# Connector.net
KiCad netlist of a schematic drawn in Altium Designer
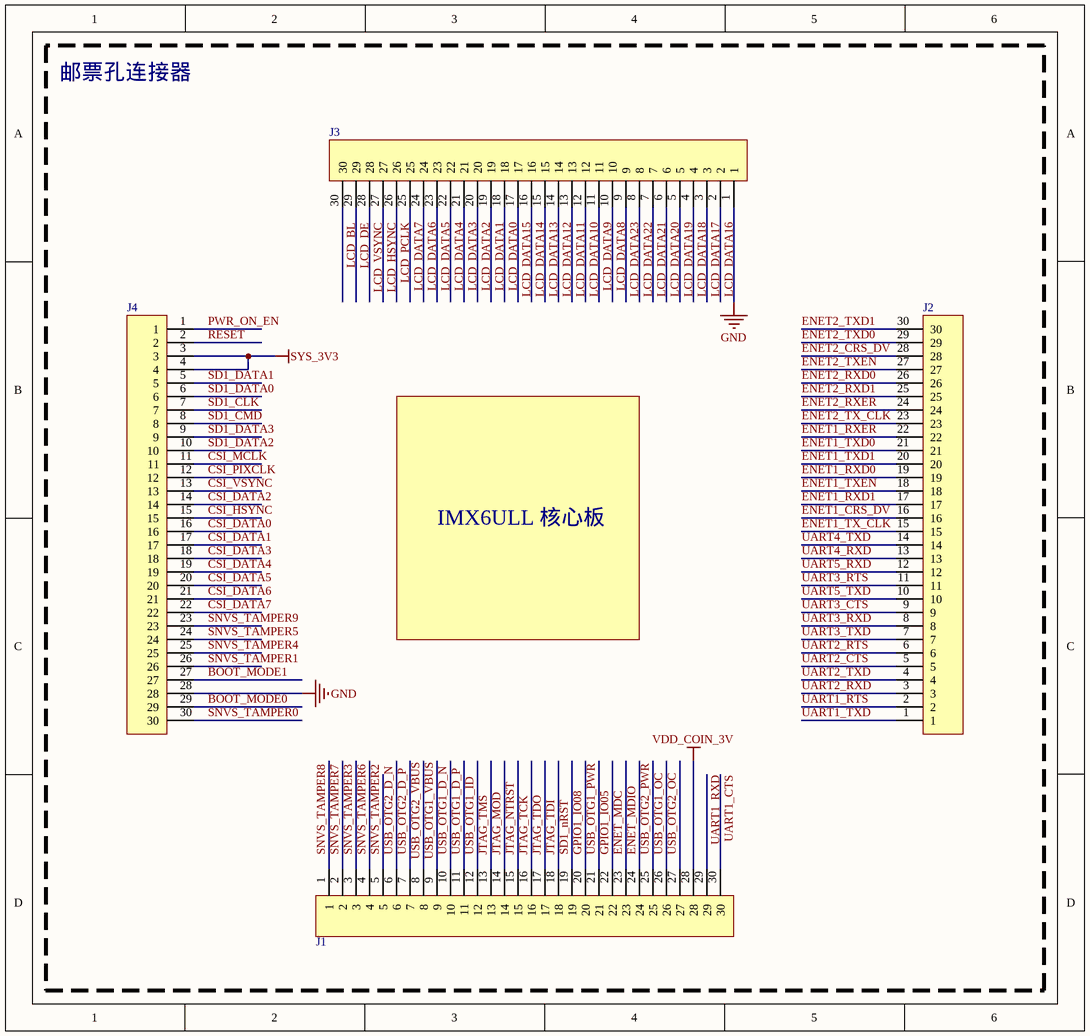
[diagram p0: Connector.SchDoc]

(export (version "E")
  (design (tool "Eeschema 10.0.6"))
  (components
    (comp (ref "J1")
      (value "stamp_hole_30")
      (footprint "STAMP_HOLE_30")
      (libsource (lib "") (part "stamp_hole_30_3"))
    )
    (comp (ref "J2")
      (value "stamp_hole_30")
      (footprint "STAMP_HOLE_30")
      (libsource (lib "Linux_Base") (part "stamp_hole_30"))
    )
    (comp (ref "J3")
      (value "stamp_hole_30")
      (footprint "STAMP_HOLE_30")
      (libsource (lib "") (part "stamp_hole_30_2"))
    )
    (comp (ref "J4")
      (value "stamp_hole_30")
      (footprint "STAMP_HOLE_30")
      (libsource (lib "") (part "stamp_hole_30_1"))
    )
  )
  (nets
    (net (code "1") (name "/BOOT_MODE0") (class "Default")
      (node (ref "J4") (pin "29") (pinfunction "29_29") (pintype "passive"))
    )
    (net (code "2") (name "/BOOT_MODE1") (class "Default")
      (node (ref "J4") (pin "27") (pinfunction "27_27") (pintype "passive"))
    )
    (net (code "3") (name "/CSI_DATA0") (class "Default")
      (node (ref "J4") (pin "16") (pinfunction "16_16") (pintype "passive"))
    )
    (net (code "4") (name "/CSI_DATA1") (class "Default")
      (node (ref "J4") (pin "17") (pinfunction "17_17") (pintype "passive"))
    )
    (net (code "5") (name "/CSI_DATA2") (class "Default")
      (node (ref "J4") (pin "14") (pinfunction "14_14") (pintype "passive"))
    )
    (net (code "6") (name "/CSI_DATA3") (class "Default")
      (node (ref "J4") (pin "18") (pinfunction "18_18") (pintype "passive"))
    )
    (net (code "7") (name "/CSI_DATA4") (class "Default")
      (node (ref "J4") (pin "19") (pinfunction "19_19") (pintype "passive"))
    )
    (net (code "8") (name "/CSI_DATA5") (class "Default")
      (node (ref "J4") (pin "20") (pinfunction "20_20") (pintype "passive"))
    )
    (net (code "9") (name "/CSI_DATA6") (class "Default")
      (node (ref "J4") (pin "21") (pinfunction "21_21") (pintype "passive"))
    )
    (net (code "10") (name "/CSI_DATA7") (class "Default")
      (node (ref "J4") (pin "22") (pinfunction "22_22") (pintype "passive"))
    )
    (net (code "11") (name "/CSI_HSYNC") (class "Default")
      (node (ref "J4") (pin "15") (pinfunction "15_15") (pintype "passive"))
    )
    (net (code "12") (name "/CSI_MCLK") (class "Default")
      (node (ref "J4") (pin "11") (pinfunction "11_11") (pintype "passive"))
    )
    (net (code "13") (name "/CSI_PIXCLK") (class "Default")
      (node (ref "J4") (pin "12") (pinfunction "12_12") (pintype "passive"))
    )
    (net (code "14") (name "/CSI_VSYNC") (class "Default")
      (node (ref "J4") (pin "13") (pinfunction "13_13") (pintype "passive"))
    )
    (net (code "15") (name "/ENET1_CRS_DV") (class "Default")
      (node (ref "J2") (pin "16") (pinfunction "16_16") (pintype "passive"))
    )
    (net (code "16") (name "/ENET1_RXD0") (class "Default")
      (node (ref "J2") (pin "19") (pinfunction "19_19") (pintype "passive"))
    )
    (net (code "17") (name "/ENET1_RXD1") (class "Default")
      (node (ref "J2") (pin "17") (pinfunction "17_17") (pintype "passive"))
    )
    (net (code "18") (name "/ENET1_RXER") (class "Default")
      (node (ref "J2") (pin "22") (pinfunction "22_22") (pintype "passive"))
    )
    (net (code "19") (name "/ENET1_TXD0") (class "Default")
      (node (ref "J2") (pin "21") (pinfunction "21_21") (pintype "passive"))
    )
    (net (code "20") (name "/ENET1_TXD1") (class "Default")
      (node (ref "J2") (pin "20") (pinfunction "20_20") (pintype "passive"))
    )
    (net (code "21") (name "/ENET1_TXEN") (class "Default")
      (node (ref "J2") (pin "18") (pinfunction "18_18") (pintype "passive"))
    )
    (net (code "22") (name "/ENET1_TX_CLK") (class "Default")
      (node (ref "J2") (pin "15") (pinfunction "15_15") (pintype "passive"))
    )
    (net (code "23") (name "/ENET2_CRS_DV") (class "Default")
      (node (ref "J2") (pin "28") (pinfunction "28_28") (pintype "passive"))
    )
    (net (code "24") (name "/ENET2_RXD0") (class "Default")
      (node (ref "J2") (pin "26") (pinfunction "26_26") (pintype "passive"))
    )
    (net (code "25") (name "/ENET2_RXD1") (class "Default")
      (node (ref "J2") (pin "25") (pinfunction "25_25") (pintype "passive"))
    )
    (net (code "26") (name "/ENET2_RXER") (class "Default")
      (node (ref "J2") (pin "24") (pinfunction "24_24") (pintype "passive"))
    )
    (net (code "27") (name "/ENET2_TXD0") (class "Default")
      (node (ref "J2") (pin "29") (pinfunction "29_29") (pintype "passive"))
    )
    (net (code "28") (name "/ENET2_TXD1") (class "Default")
      (node (ref "J2") (pin "30") (pinfunction "30_30") (pintype "passive"))
    )
    (net (code "29") (name "/ENET2_TXEN") (class "Default")
      (node (ref "J2") (pin "27") (pinfunction "27_27") (pintype "passive"))
    )
    (net (code "30") (name "/ENET2_TX_CLK") (class "Default")
      (node (ref "J2") (pin "23") (pinfunction "23_23") (pintype "passive"))
    )
    (net (code "31") (name "/ENET_MDC") (class "Default")
      (node (ref "J1") (pin "23") (pinfunction "23_23") (pintype "passive"))
    )
    (net (code "32") (name "/ENET_MDIO") (class "Default")
      (node (ref "J1") (pin "24") (pinfunction "24_24") (pintype "passive"))
    )
    (net (code "33") (name "/GPIO1_IO05") (class "Default")
      (node (ref "J1") (pin "22") (pinfunction "22_22") (pintype "passive"))
    )
    (net (code "34") (name "/GPIO1_IO08") (class "Default")
      (node (ref "J1") (pin "20") (pinfunction "20_20") (pintype "passive"))
    )
    (net (code "35") (name "/JTAG_MOD") (class "Default")
      (node (ref "J1") (pin "14") (pinfunction "14_14") (pintype "passive"))
    )
    (net (code "36") (name "/JTAG_NTRST") (class "Default")
      (node (ref "J1") (pin "15") (pinfunction "15_15") (pintype "passive"))
    )
    (net (code "37") (name "/JTAG_TCK") (class "Default")
      (node (ref "J1") (pin "16") (pinfunction "16_16") (pintype "passive"))
    )
    (net (code "38") (name "/JTAG_TDI") (class "Default")
      (node (ref "J1") (pin "18") (pinfunction "18_18") (pintype "passive"))
    )
    (net (code "39") (name "/JTAG_TDO") (class "Default")
      (node (ref "J1") (pin "17") (pinfunction "17_17") (pintype "passive"))
    )
    (net (code "40") (name "/JTAG_TMS") (class "Default")
      (node (ref "J1") (pin "13") (pinfunction "13_13") (pintype "passive"))
    )
    (net (code "41") (name "/LCD_BL") (class "Default")
      (node (ref "J3") (pin "30") (pinfunction "30_30") (pintype "passive"))
    )
    (net (code "42") (name "/LCD_DATA0") (class "Default")
      (node (ref "J3") (pin "18") (pinfunction "18_18") (pintype "passive"))
    )
    (net (code "43") (name "/LCD_DATA1") (class "Default")
      (node (ref "J3") (pin "19") (pinfunction "19_19") (pintype "passive"))
    )
    (net (code "44") (name "/LCD_DATA2") (class "Default")
      (node (ref "J3") (pin "20") (pinfunction "20_20") (pintype "passive"))
    )
    (net (code "45") (name "/LCD_DATA3") (class "Default")
      (node (ref "J3") (pin "21") (pinfunction "21_21") (pintype "passive"))
    )
    (net (code "46") (name "/LCD_DATA4") (class "Default")
      (node (ref "J3") (pin "22") (pinfunction "22_22") (pintype "passive"))
    )
    (net (code "47") (name "/LCD_DATA5") (class "Default")
      (node (ref "J3") (pin "23") (pinfunction "23_23") (pintype "passive"))
    )
    (net (code "48") (name "/LCD_DATA6") (class "Default")
      (node (ref "J3") (pin "24") (pinfunction "24_24") (pintype "passive"))
    )
    (net (code "49") (name "/LCD_DATA7") (class "Default")
      (node (ref "J3") (pin "25") (pinfunction "25_25") (pintype "passive"))
    )
    (net (code "50") (name "/LCD_DATA8") (class "Default")
      (node (ref "J3") (pin "10") (pinfunction "10_10") (pintype "passive"))
    )
    (net (code "51") (name "/LCD_DATA9") (class "Default")
      (node (ref "J3") (pin "11") (pinfunction "11_11") (pintype "passive"))
    )
    (net (code "52") (name "/LCD_DATA10") (class "Default")
      (node (ref "J3") (pin "12") (pinfunction "12_12") (pintype "passive"))
    )
    (net (code "53") (name "/LCD_DATA11") (class "Default")
      (node (ref "J3") (pin "13") (pinfunction "13_13") (pintype "passive"))
    )
    (net (code "54") (name "/LCD_DATA12") (class "Default")
      (node (ref "J3") (pin "14") (pinfunction "14_14") (pintype "passive"))
    )
    (net (code "55") (name "/LCD_DATA13") (class "Default")
      (node (ref "J3") (pin "15") (pinfunction "15_15") (pintype "passive"))
    )
    (net (code "56") (name "/LCD_DATA14") (class "Default")
      (node (ref "J3") (pin "16") (pinfunction "16_16") (pintype "passive"))
    )
    (net (code "57") (name "/LCD_DATA15") (class "Default")
      (node (ref "J3") (pin "17") (pinfunction "17_17") (pintype "passive"))
    )
    (net (code "58") (name "/LCD_DATA16") (class "Default")
      (node (ref "J3") (pin "2") (pinfunction "2_2") (pintype "passive"))
    )
    (net (code "59") (name "/LCD_DATA17") (class "Default")
      (node (ref "J3") (pin "3") (pinfunction "3_3") (pintype "passive"))
    )
    (net (code "60") (name "/LCD_DATA18") (class "Default")
      (node (ref "J3") (pin "4") (pinfunction "4_4") (pintype "passive"))
    )
    (net (code "61") (name "/LCD_DATA19") (class "Default")
      (node (ref "J3") (pin "5") (pinfunction "5_5") (pintype "passive"))
    )
    (net (code "62") (name "/LCD_DATA20") (class "Default")
      (node (ref "J3") (pin "6") (pinfunction "6_6") (pintype "passive"))
    )
    (net (code "63") (name "/LCD_DATA21") (class "Default")
      (node (ref "J3") (pin "7") (pinfunction "7_7") (pintype "passive"))
    )
    (net (code "64") (name "/LCD_DATA22") (class "Default")
      (node (ref "J3") (pin "8") (pinfunction "8_8") (pintype "passive"))
    )
    (net (code "65") (name "/LCD_DATA23") (class "Default")
      (node (ref "J3") (pin "9") (pinfunction "9_9") (pintype "passive"))
    )
    (net (code "66") (name "/LCD_DE") (class "Default")
      (node (ref "J3") (pin "29") (pinfunction "29_29") (pintype "passive"))
    )
    (net (code "67") (name "/LCD_HSYNC") (class "Default")
      (node (ref "J3") (pin "27") (pinfunction "27_27") (pintype "passive"))
    )
    (net (code "68") (name "/LCD_PCLK") (class "Default")
      (node (ref "J3") (pin "26") (pinfunction "26_26") (pintype "passive"))
    )
    (net (code "69") (name "/LCD_VSYNC") (class "Default")
      (node (ref "J3") (pin "28") (pinfunction "28_28") (pintype "passive"))
    )
    (net (code "70") (name "/PWR_ON_EN") (class "Default")
      (node (ref "J4") (pin "1") (pinfunction "1_1") (pintype "passive"))
    )
    (net (code "71") (name "/RESET") (class "Default")
      (node (ref "J4") (pin "2") (pinfunction "2_2") (pintype "passive"))
    )
    (net (code "72") (name "/SD1_CLK") (class "Default")
      (node (ref "J4") (pin "7") (pinfunction "7_7") (pintype "passive"))
    )
    (net (code "73") (name "/SD1_CMD") (class "Default")
      (node (ref "J4") (pin "8") (pinfunction "8_8") (pintype "passive"))
    )
    (net (code "74") (name "/SD1_DATA0") (class "Default")
      (node (ref "J4") (pin "6") (pinfunction "6_6") (pintype "passive"))
    )
    (net (code "75") (name "/SD1_DATA1") (class "Default")
      (node (ref "J4") (pin "5") (pinfunction "5_5") (pintype "passive"))
    )
    (net (code "76") (name "/SD1_DATA2") (class "Default")
      (node (ref "J4") (pin "10") (pinfunction "10_10") (pintype "passive"))
    )
    (net (code "77") (name "/SD1_DATA3") (class "Default")
      (node (ref "J4") (pin "9") (pinfunction "9_9") (pintype "passive"))
    )
    (net (code "78") (name "/SD1_nRST") (class "Default")
      (node (ref "J1") (pin "19") (pinfunction "19_19") (pintype "passive"))
    )
    (net (code "79") (name "/SNVS_TAMPER0") (class "Default")
      (node (ref "J4") (pin "30") (pinfunction "30_30") (pintype "passive"))
    )
    (net (code "80") (name "/SNVS_TAMPER1") (class "Default")
      (node (ref "J4") (pin "26") (pinfunction "26_26") (pintype "passive"))
    )
    (net (code "81") (name "/SNVS_TAMPER2") (class "Default")
      (node (ref "J1") (pin "5") (pinfunction "5_5") (pintype "passive"))
    )
    (net (code "82") (name "/SNVS_TAMPER3") (class "Default")
      (node (ref "J1") (pin "3") (pinfunction "3_3") (pintype "passive"))
    )
    (net (code "83") (name "/SNVS_TAMPER4") (class "Default")
      (node (ref "J4") (pin "25") (pinfunction "25_25") (pintype "passive"))
    )
    (net (code "84") (name "/SNVS_TAMPER5") (class "Default")
      (node (ref "J4") (pin "24") (pinfunction "24_24") (pintype "passive"))
    )
    (net (code "85") (name "/SNVS_TAMPER6") (class "Default")
      (node (ref "J1") (pin "4") (pinfunction "4_4") (pintype "passive"))
    )
    (net (code "86") (name "/SNVS_TAMPER7") (class "Default")
      (node (ref "J1") (pin "2") (pinfunction "2_2") (pintype "passive"))
    )
    (net (code "87") (name "/SNVS_TAMPER8") (class "Default")
      (node (ref "J1") (pin "1") (pinfunction "1_1") (pintype "passive"))
    )
    (net (code "88") (name "/SNVS_TAMPER9") (class "Default")
      (node (ref "J4") (pin "23") (pinfunction "23_23") (pintype "passive"))
    )
    (net (code "89") (name "/UART1_CTS") (class "Default")
      (node (ref "J1") (pin "30") (pinfunction "30_30") (pintype "passive"))
    )
    (net (code "90") (name "/UART1_RTS") (class "Default")
      (node (ref "J2") (pin "2") (pinfunction "2_2") (pintype "passive"))
    )
    (net (code "91") (name "/UART1_RXD") (class "Default")
      (node (ref "J1") (pin "29") (pinfunction "29_29") (pintype "passive"))
    )
    (net (code "92") (name "/UART1_TXD") (class "Default")
      (node (ref "J2") (pin "1") (pinfunction "1_1") (pintype "passive"))
    )
    (net (code "93") (name "/UART2_CTS") (class "Default")
      (node (ref "J2") (pin "5") (pinfunction "5_5") (pintype "passive"))
    )
    (net (code "94") (name "/UART2_RTS") (class "Default")
      (node (ref "J2") (pin "6") (pinfunction "6_6") (pintype "passive"))
    )
    (net (code "95") (name "/UART2_RXD") (class "Default")
      (node (ref "J2") (pin "3") (pinfunction "3_3") (pintype "passive"))
    )
    (net (code "96") (name "/UART2_TXD") (class "Default")
      (node (ref "J2") (pin "4") (pinfunction "4_4") (pintype "passive"))
    )
    (net (code "97") (name "/UART3_CTS") (class "Default")
      (node (ref "J2") (pin "9") (pinfunction "9_9") (pintype "passive"))
    )
    (net (code "98") (name "/UART3_RTS") (class "Default")
      (node (ref "J2") (pin "11") (pinfunction "11_11") (pintype "passive"))
    )
    (net (code "99") (name "/UART3_RXD") (class "Default")
      (node (ref "J2") (pin "8") (pinfunction "8_8") (pintype "passive"))
    )
    (net (code "100") (name "/UART3_TXD") (class "Default")
      (node (ref "J2") (pin "7") (pinfunction "7_7") (pintype "passive"))
    )
    (net (code "101") (name "/UART4_RXD") (class "Default")
      (node (ref "J2") (pin "13") (pinfunction "13_13") (pintype "passive"))
    )
    (net (code "102") (name "/UART4_TXD") (class "Default")
      (node (ref "J2") (pin "14") (pinfunction "14_14") (pintype "passive"))
    )
    (net (code "103") (name "/UART5_RXD") (class "Default")
      (node (ref "J2") (pin "12") (pinfunction "12_12") (pintype "passive"))
    )
    (net (code "104") (name "/UART5_TXD") (class "Default")
      (node (ref "J2") (pin "10") (pinfunction "10_10") (pintype "passive"))
    )
    (net (code "105") (name "/USB_OTG1_D_N") (class "Default")
      (node (ref "J1") (pin "10") (pinfunction "10_10") (pintype "passive"))
    )
    (net (code "106") (name "/USB_OTG1_D_P") (class "Default")
      (node (ref "J1") (pin "11") (pinfunction "11_11") (pintype "passive"))
    )
    (net (code "107") (name "/USB_OTG1_ID") (class "Default")
      (node (ref "J1") (pin "12") (pinfunction "12_12") (pintype "passive"))
    )
    (net (code "108") (name "/USB_OTG1_OC") (class "Default")
      (node (ref "J1") (pin "26") (pinfunction "26_26") (pintype "passive"))
    )
    (net (code "109") (name "/USB_OTG1_PWR") (class "Default")
      (node (ref "J1") (pin "21") (pinfunction "21_21") (pintype "passive"))
    )
    (net (code "110") (name "/USB_OTG1_VBUS") (class "Default")
      (node (ref "J1") (pin "9") (pinfunction "9_9") (pintype "passive"))
    )
    (net (code "111") (name "/USB_OTG2_D_N") (class "Default")
      (node (ref "J1") (pin "6") (pinfunction "6_6") (pintype "passive"))
    )
    (net (code "112") (name "/USB_OTG2_D_P") (class "Default")
      (node (ref "J1") (pin "7") (pinfunction "7_7") (pintype "passive"))
    )
    (net (code "113") (name "/USB_OTG2_OC") (class "Default")
      (node (ref "J1") (pin "27") (pinfunction "27_27") (pintype "passive"))
    )
    (net (code "114") (name "/USB_OTG2_PWR") (class "Default")
      (node (ref "J1") (pin "25") (pinfunction "25_25") (pintype "passive"))
    )
    (net (code "115") (name "/USB_OTG2_VBUS") (class "Default")
      (node (ref "J1") (pin "8") (pinfunction "8_8") (pintype "passive"))
    )
    (net (code "116") (name "GND") (class "Default")
      (node (ref "J3") (pin "1") (pinfunction "1_1") (pintype "passive"))
      (node (ref "J4") (pin "28") (pinfunction "28_28") (pintype "passive"))
    )
    (net (code "117") (name "SYS_3V3") (class "Default")
      (node (ref "J4") (pin "3") (pinfunction "3_3") (pintype "passive"))
      (node (ref "J4") (pin "4") (pinfunction "4_4") (pintype "passive"))
    )
    (net (code "118") (name "VDD_COIN_3V") (class "Default")
      (node (ref "J1") (pin "28") (pinfunction "28_28") (pintype "passive"))
    )
  )
)
